# Pong_final.net
KiCad netlist of a schematic drawn in EAGLE
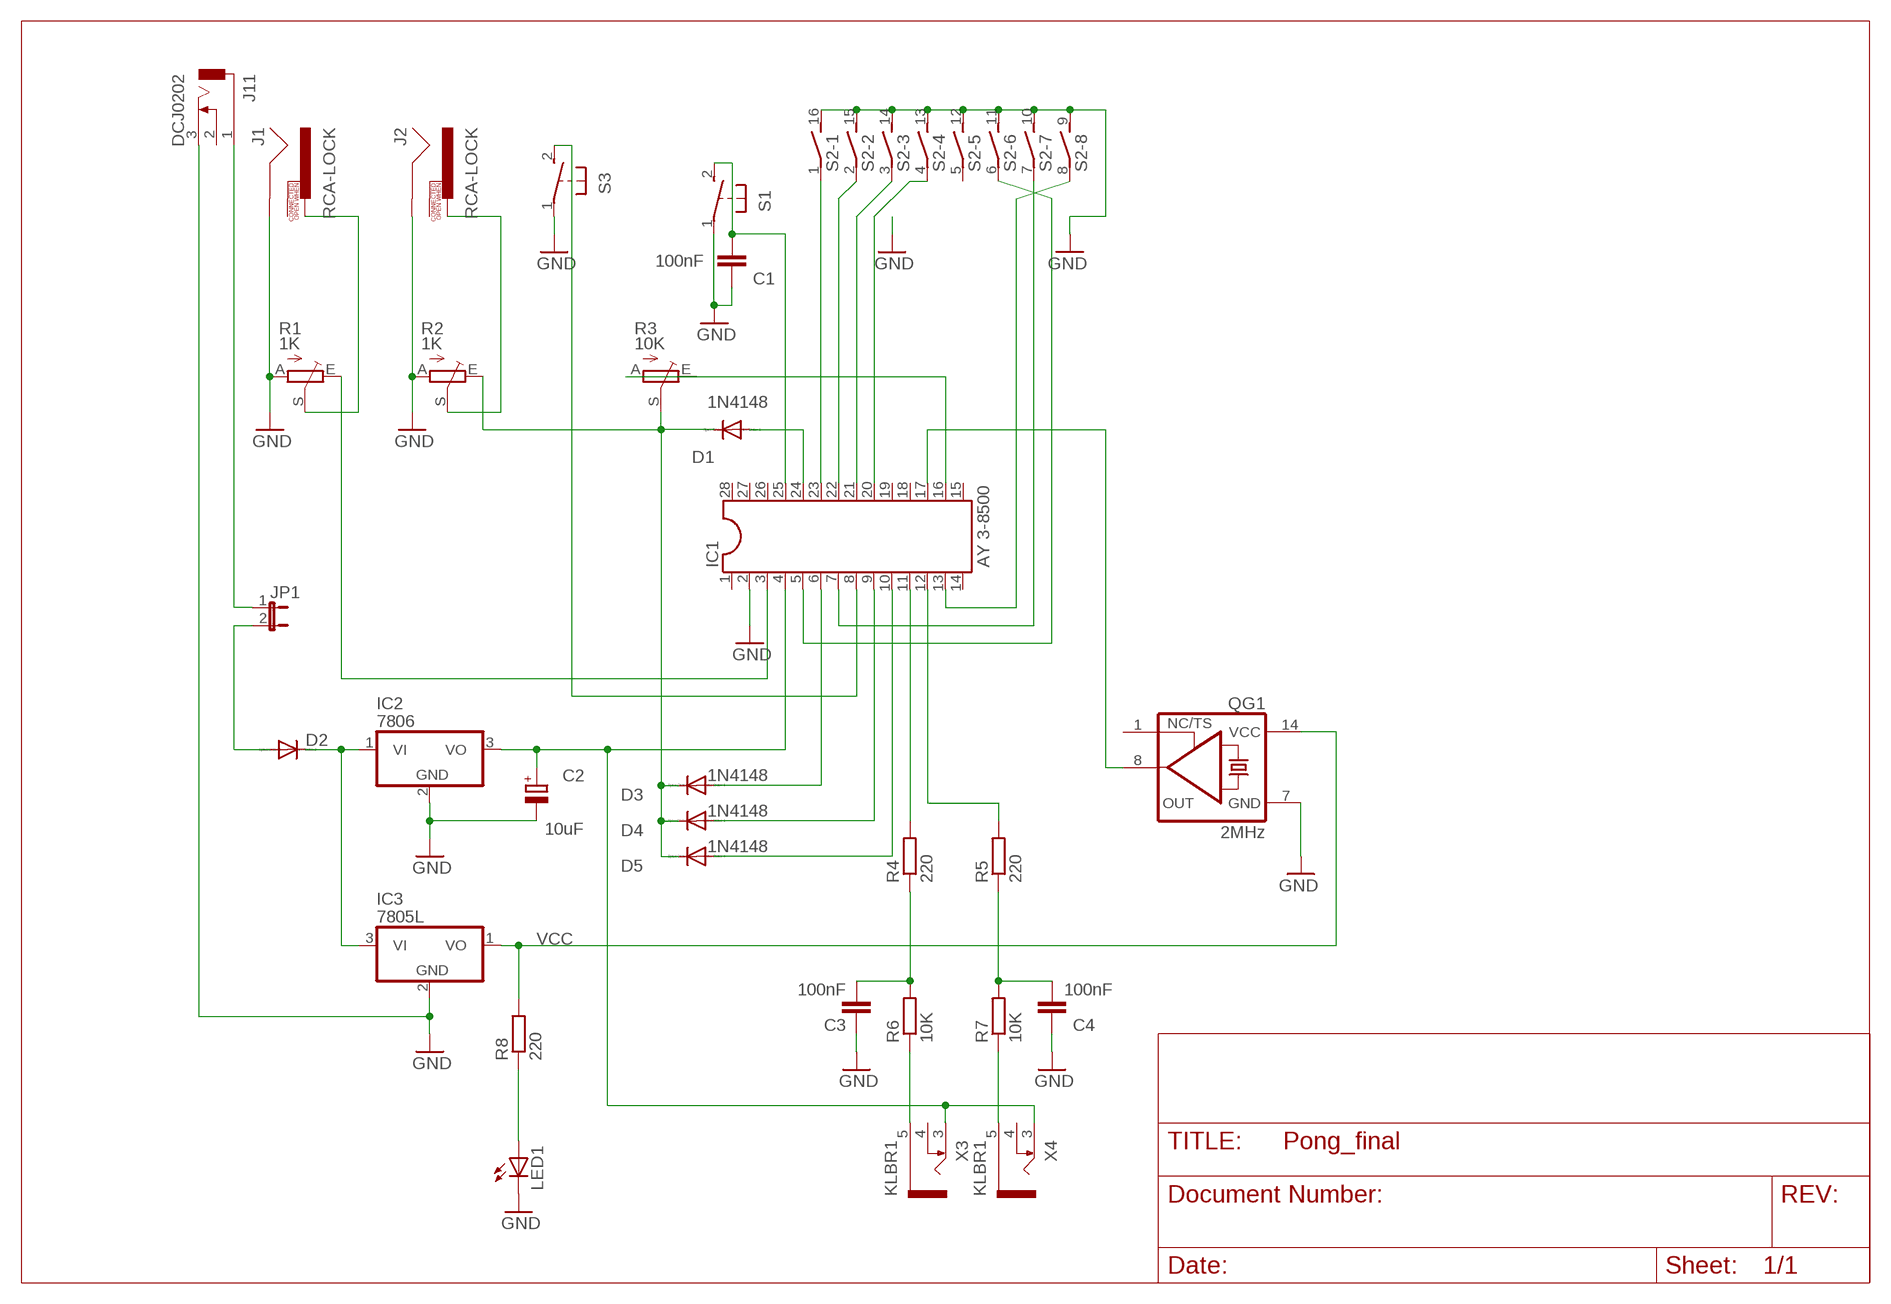
[diagram p0: schematic, sheet 1]

(export (version "E")
  (design (tool "Eeschema 10.0.6"))
  (components
    (comp (ref "C1")
      (value "100nF")
      (footprint "eagle-import:C0805")
      (libsource (lib "eagle-import") (part "C-EUC0805"))
    )
    (comp (ref "C2")
      (value "10uF")
      (footprint "eagle-import:E2,5-6")
      (libsource (lib "eagle-import") (part "CPOL-EUE2.5-6"))
    )
    (comp (ref "C3")
      (value "100nF")
      (footprint "eagle-import:C0805K")
      (libsource (lib "eagle-import") (part "C-EUC0805K"))
    )
    (comp (ref "C4")
      (value "100nF")
      (footprint "eagle-import:C0805K")
      (libsource (lib "eagle-import") (part "C-EUC0805K"))
    )
    (comp (ref "D1")
      (value "1N4148")
      (footprint "eagle-import:MINIMELF")
      (libsource (lib "eagle-import") (part "DIODE-MINIMELF"))
    )
    (comp (ref "D2")
      (value "DIODE-MELF-MLL41")
      (footprint "eagle-import:MELF-MLL41")
      (libsource (lib "eagle-import") (part "DIODE-MELF-MLL41"))
    )
    (comp (ref "D3")
      (value "1N4148")
      (footprint "eagle-import:MINIMELF")
      (libsource (lib "eagle-import") (part "DIODE-MINIMELF"))
    )
    (comp (ref "D4")
      (value "1N4148")
      (footprint "eagle-import:MINIMELF")
      (libsource (lib "eagle-import") (part "DIODE-MINIMELF"))
    )
    (comp (ref "D5")
      (value "1N4148")
      (footprint "eagle-import:MINIMELF")
      (libsource (lib "eagle-import") (part "DIODE-MINIMELF"))
    )
    (comp (ref "IC1")
      (value "AY 3-8500")
      (footprint "eagle-import:DIL28-6")
      (libsource (lib "eagle-import") (part "DIL28"))
    )
    (comp (ref "IC2")
      (value "7806")
      (footprint "eagle-import:TO220V")
      (libsource (lib "eagle-import") (part "78TV05"))
    )
    (comp (ref "IC3")
      (value "7805L")
      (footprint "eagle-import:TO92")
      (libsource (lib "eagle-import") (part "78L05"))
    )
    (comp (ref "J1")
      (value "RCA-LOCK")
      (footprint "eagle-import:RCA_LOCK")
      (libsource (lib "eagle-import") (part "RCA-LOCK"))
    )
    (comp (ref "J2")
      (value "RCA-LOCK")
      (footprint "eagle-import:RCA_LOCK")
      (libsource (lib "eagle-import") (part "RCA-LOCK"))
    )
    (comp (ref "J11")
      (value "DCJ0202")
      (footprint "eagle-import:DCJ0202")
      (libsource (lib "eagle-import") (part "DCJ0202"))
    )
    (comp (ref "JP1")
      (value "JP1E")
      (footprint "eagle-import:JP1")
      (libsource (lib "eagle-import") (part "JP1E"))
    )
    (comp (ref "LED1")
      (value "LEDB155")
      (footprint "eagle-import:Q62902-B155")
      (libsource (lib "eagle-import") (part "LEDB155"))
    )
    (comp (ref "QG1")
      (value "2MHz")
      (footprint "eagle-import:DIL14S")
      (libsource (lib "eagle-import") (part "XO-14"))
    )
    (comp (ref "R1")
      (value "1K")
      (footprint "eagle-import:CA6V")
      (libsource (lib "eagle-import") (part "TRIM_EU-CA6V"))
    )
    (comp (ref "R2")
      (value "1K")
      (footprint "eagle-import:CA6V")
      (libsource (lib "eagle-import") (part "TRIM_EU-CA6V"))
    )
    (comp (ref "R3")
      (value "10K")
      (footprint "eagle-import:CA6V")
      (libsource (lib "eagle-import") (part "TRIM_EU-CA6V"))
    )
    (comp (ref "R4")
      (value "220")
      (footprint "eagle-import:R0805")
      (libsource (lib "eagle-import") (part "R-EU_R0805"))
    )
    (comp (ref "R5")
      (value "220")
      (footprint "eagle-import:R0805")
      (libsource (lib "eagle-import") (part "R-EU_R0805"))
    )
    (comp (ref "R6")
      (value "10K")
      (footprint "eagle-import:R0805")
      (libsource (lib "eagle-import") (part "R-EU_R0805"))
    )
    (comp (ref "R7")
      (value "10K")
      (footprint "eagle-import:R0805")
      (libsource (lib "eagle-import") (part "R-EU_R0805"))
    )
    (comp (ref "R8")
      (value "220")
      (footprint "eagle-import:R0805")
      (libsource (lib "eagle-import") (part "R-EU_R0805"))
    )
    (comp (ref "S1")
      (value "31-XX")
      (footprint "eagle-import:B3F-31XX")
      (fields (field (name "MPN") "B3F-3100"))
      (libsource (lib "eagle-import") (part "31-XX"))
    )
    (comp (ref "S2")
      (value "DIP08S")
      (footprint "eagle-import:DIP08S")
      (libsource (lib "eagle-import") (part "DIP08S"))
    )
    (comp (ref "S3")
      (value "31-XX")
      (footprint "eagle-import:B3F-31XX")
      (fields (field (name "MPN") "B3F-3100"))
      (libsource (lib "eagle-import") (part "31-XX"))
    )
    (comp (ref "X3")
      (value "KLBR1")
      (footprint "eagle-import:KLBR1")
      (fields (field (name "MPN") "KLBR 1"))
      (libsource (lib "eagle-import") (part "KLBR?1"))
    )
    (comp (ref "X4")
      (value "KLBR1")
      (footprint "eagle-import:KLBR1")
      (fields (field (name "MPN") "KLBR 1"))
      (libsource (lib "eagle-import") (part "KLBR?1"))
    )
  )
  (nets
    (net (code "1") (name "/VCC") (class "Default")
      (node (ref "IC3") (pin "1") (pinfunction "VO_1") (pintype "passive"))
      (node (ref "QG1") (pin "14") (pinfunction "VCC_14") (pintype "power_in"))
      (node (ref "R8") (pin "2") (pinfunction "2_2") (pintype "passive"))
    )
    (net (code "2") (name "GND") (class "Default")
      (node (ref "C1") (pin "1") (pinfunction "1_1") (pintype "passive"))
      (node (ref "C2") (pin "-") (pinfunction "-_-") (pintype "passive"))
      (node (ref "C3") (pin "1") (pinfunction "1_1") (pintype "passive"))
      (node (ref "C4") (pin "1") (pinfunction "1_1") (pintype "passive"))
      (node (ref "IC1") (pin "2") (pinfunction "2_2") (pintype "passive"))
      (node (ref "IC2") (pin "2") (pinfunction "GND_2") (pintype "passive"))
      (node (ref "IC3") (pin "2") (pinfunction "GND_2") (pintype "passive"))
      (node (ref "J1") (pin "SHELL") (pinfunction "SHELL_SHELL") (pintype "bidirectional"))
      (node (ref "J11") (pin "3") (pinfunction "3_3") (pintype "passive"))
      (node (ref "J2") (pin "SHELL") (pinfunction "SHELL_SHELL") (pintype "bidirectional"))
      (node (ref "LED1") (pin "K") (pinfunction "C_K") (pintype "passive"))
      (node (ref "QG1") (pin "7") (pinfunction "GND_7") (pintype "power_in"))
      (node (ref "R1") (pin "A") (pinfunction "A_A") (pintype "passive"))
      (node (ref "R2") (pin "A") (pinfunction "A_A") (pintype "passive"))
      (node (ref "S1") (pin "1") (pinfunction "P_1") (pintype "passive"))
      (node (ref "S2") (pin "10") (pinfunction "2_10") (pintype "passive"))
      (node (ref "S2") (pin "11") (pinfunction "2_11") (pintype "passive"))
      (node (ref "S2") (pin "12") (pinfunction "2_12") (pintype "passive"))
      (node (ref "S2") (pin "13") (pinfunction "2_13") (pintype "passive"))
      (node (ref "S2") (pin "14") (pinfunction "2_14") (pintype "passive"))
      (node (ref "S2") (pin "15") (pinfunction "2_15") (pintype "passive"))
      (node (ref "S2") (pin "16") (pinfunction "2_16") (pintype "passive"))
      (node (ref "S2") (pin "9") (pinfunction "2_9") (pintype "passive"))
      (node (ref "S3") (pin "1") (pinfunction "P_1") (pintype "passive"))
    )
    (net (code "3") (name "Net-(C3-Pad2)") (class "Default")
      (node (ref "C3") (pin "2") (pinfunction "2_2") (pintype "passive"))
      (node (ref "R4") (pin "1") (pinfunction "1_1") (pintype "passive"))
      (node (ref "R6") (pin "2") (pinfunction "2_2") (pintype "passive"))
    )
    (net (code "4") (name "Net-(C4-Pad2)") (class "Default")
      (node (ref "C4") (pin "2") (pinfunction "2_2") (pintype "passive"))
      (node (ref "R5") (pin "1") (pinfunction "1_1") (pintype "passive"))
      (node (ref "R7") (pin "2") (pinfunction "2_2") (pintype "passive"))
    )
    (net (code "5") (name "Net-(D1-PadA)") (class "Default")
      (node (ref "D1") (pin "A") (pinfunction "A_A") (pintype "passive"))
      (node (ref "IC1") (pin "24") (pinfunction "24_24") (pintype "passive"))
    )
    (net (code "6") (name "Net-(D1-PadC)") (class "Default")
      (node (ref "D1") (pin "C") (pinfunction "C_C") (pintype "passive"))
      (node (ref "D3") (pin "C") (pinfunction "C_C") (pintype "passive"))
      (node (ref "D4") (pin "C") (pinfunction "C_C") (pintype "passive"))
      (node (ref "D5") (pin "C") (pinfunction "C_C") (pintype "passive"))
      (node (ref "R2") (pin "E") (pinfunction "E_E") (pintype "passive"))
      (node (ref "R3") (pin "S") (pinfunction "S_S") (pintype "passive"))
    )
    (net (code "7") (name "Net-(D2-PadA)") (class "Default")
      (node (ref "D2") (pin "A") (pinfunction "A_A") (pintype "passive"))
      (node (ref "JP1") (pin "2") (pinfunction "2_2") (pintype "passive"))
    )
    (net (code "8") (name "Net-(D3-PadA)") (class "Default")
      (node (ref "D3") (pin "A") (pinfunction "A_A") (pintype "passive"))
      (node (ref "IC1") (pin "6") (pinfunction "6_6") (pintype "passive"))
    )
    (net (code "9") (name "Net-(D4-PadA)") (class "Default")
      (node (ref "D4") (pin "A") (pinfunction "A_A") (pintype "passive"))
      (node (ref "IC1") (pin "9") (pinfunction "9_9") (pintype "passive"))
    )
    (net (code "10") (name "Net-(D5-PadA)") (class "Default")
      (node (ref "D5") (pin "A") (pinfunction "A_A") (pintype "passive"))
      (node (ref "IC1") (pin "10") (pinfunction "10_10") (pintype "passive"))
    )
    (net (code "11") (name "Net-(IC1-Pad3)") (class "Default")
      (node (ref "IC1") (pin "3") (pinfunction "3_3") (pintype "passive"))
      (node (ref "R1") (pin "E") (pinfunction "E_E") (pintype "passive"))
    )
    (net (code "12") (name "Net-(IC1-Pad11)") (class "Default")
      (node (ref "IC1") (pin "11") (pinfunction "11_11") (pintype "passive"))
      (node (ref "R4") (pin "2") (pinfunction "2_2") (pintype "passive"))
    )
    (net (code "13") (name "Net-(IC1-Pad12)") (class "Default")
      (node (ref "IC1") (pin "12") (pinfunction "12_12") (pintype "passive"))
      (node (ref "R5") (pin "2") (pinfunction "2_2") (pintype "passive"))
    )
    (net (code "14") (name "Net-(IC1-Pad16)") (class "Default")
      (node (ref "IC1") (pin "16") (pinfunction "16_16") (pintype "passive"))
      (node (ref "R3") (pin "A") (pinfunction "A_A") (pintype "passive"))
    )
    (net (code "15") (name "Net-(IC1-Pad23)") (class "Default")
      (node (ref "IC1") (pin "23") (pinfunction "23_23") (pintype "passive"))
      (node (ref "S2") (pin "1") (pinfunction "1_1") (pintype "passive"))
    )
    (net (code "16") (name "Net-(IC2-VI)") (class "Default")
      (node (ref "D2") (pin "C") (pinfunction "C_C") (pintype "passive"))
      (node (ref "IC2") (pin "1") (pinfunction "VI_1") (pintype "input"))
      (node (ref "IC3") (pin "3") (pinfunction "VI_3") (pintype "input"))
    )
    (net (code "17") (name "Net-(IC2-VO)") (class "Default")
      (node (ref "C2") (pin "+") (pinfunction "+_+") (pintype "passive"))
      (node (ref "IC1") (pin "4") (pinfunction "4_4") (pintype "passive"))
      (node (ref "IC2") (pin "3") (pinfunction "VO_3") (pintype "passive"))
      (node (ref "X3") (pin "3") (pinfunction "3_3") (pintype "passive"))
      (node (ref "X4") (pin "3") (pinfunction "3_3") (pintype "passive"))
    )
    (net (code "18") (name "Net-(J1-PadPIN)") (class "Default")
      (node (ref "J1") (pin "PIN") (pinfunction "PIN_PIN") (pintype "bidirectional"))
      (node (ref "R1") (pin "S") (pinfunction "S_S") (pintype "passive"))
    )
    (net (code "19") (name "Net-(J2-PadPIN)") (class "Default")
      (node (ref "J2") (pin "PIN") (pinfunction "PIN_PIN") (pintype "bidirectional"))
      (node (ref "R2") (pin "S") (pinfunction "S_S") (pintype "passive"))
    )
    (net (code "20") (name "Net-(J11-Pad1)") (class "Default")
      (node (ref "J11") (pin "1") (pinfunction "1_1") (pintype "passive"))
      (node (ref "JP1") (pin "1") (pinfunction "1_1") (pintype "passive"))
    )
    (net (code "21") (name "Net-(LED1-PadA)") (class "Default")
      (node (ref "LED1") (pin "A") (pinfunction "A_A") (pintype "passive"))
      (node (ref "R8") (pin "1") (pinfunction "1_1") (pintype "passive"))
    )
    (net (code "22") (name "Net-(QG1-OUT)") (class "Default")
      (node (ref "IC1") (pin "17") (pinfunction "17_17") (pintype "passive"))
      (node (ref "QG1") (pin "8") (pinfunction "OUT_8") (pintype "output"))
    )
    (net (code "23") (name "Net-(R6-Pad1)") (class "Default")
      (node (ref "R6") (pin "1") (pinfunction "1_1") (pintype "passive"))
      (node (ref "X3") (pin "5") (pinfunction "5_5") (pintype "passive"))
    )
    (net (code "24") (name "Net-(R7-Pad1)") (class "Default")
      (node (ref "R7") (pin "1") (pinfunction "1_1") (pintype "passive"))
      (node (ref "X4") (pin "5") (pinfunction "5_5") (pintype "passive"))
    )
    (net (code "25") (name "Net-(S1-S)") (class "Default")
      (node (ref "C1") (pin "2") (pinfunction "2_2") (pintype "passive"))
      (node (ref "IC1") (pin "25") (pinfunction "25_25") (pintype "passive"))
      (node (ref "S1") (pin "2") (pinfunction "S_2") (pintype "passive"))
    )
    (net (code "26") (name "Net-(S2B-1)") (class "Default")
      (node (ref "IC1") (pin "22") (pinfunction "22_22") (pintype "passive"))
      (node (ref "S2") (pin "2") (pinfunction "1_2") (pintype "passive"))
    )
    (net (code "27") (name "Net-(S2C-1)") (class "Default")
      (node (ref "IC1") (pin "21") (pinfunction "21_21") (pintype "passive"))
      (node (ref "S2") (pin "3") (pinfunction "1_3") (pintype "passive"))
    )
    (net (code "28") (name "Net-(S2D-1)") (class "Default")
      (node (ref "IC1") (pin "20") (pinfunction "20_20") (pintype "passive"))
      (node (ref "S2") (pin "4") (pinfunction "1_4") (pintype "passive"))
    )
    (net (code "29") (name "Net-(S2F-1)") (class "Default")
      (node (ref "IC1") (pin "5") (pinfunction "5_5") (pintype "passive"))
      (node (ref "S2") (pin "6") (pinfunction "1_6") (pintype "passive"))
    )
    (net (code "30") (name "Net-(S2G-1)") (class "Default")
      (node (ref "IC1") (pin "7") (pinfunction "7_7") (pintype "passive"))
      (node (ref "S2") (pin "7") (pinfunction "1_7") (pintype "passive"))
    )
    (net (code "31") (name "Net-(S2H-1)") (class "Default")
      (node (ref "IC1") (pin "13") (pinfunction "13_13") (pintype "passive"))
      (node (ref "S2") (pin "8") (pinfunction "1_8") (pintype "passive"))
    )
    (net (code "32") (name "Net-(S3-S)") (class "Default")
      (node (ref "IC1") (pin "8") (pinfunction "8_8") (pintype "passive"))
      (node (ref "S3") (pin "2") (pinfunction "S_2") (pintype "passive"))
    )
    (net (code "33") (name "unconnected-(IC1-Pad1)") (class "Default")
      (node (ref "IC1") (pin "1") (pinfunction "1_1") (pintype "passive"))
    )
    (net (code "34") (name "unconnected-(IC1-Pad14)") (class "Default")
      (node (ref "IC1") (pin "14") (pinfunction "14_14") (pintype "passive"))
    )
    (net (code "35") (name "unconnected-(IC1-Pad15)") (class "Default")
      (node (ref "IC1") (pin "15") (pinfunction "15_15") (pintype "passive"))
    )
    (net (code "36") (name "unconnected-(IC1-Pad18)") (class "Default")
      (node (ref "IC1") (pin "18") (pinfunction "18_18") (pintype "passive"))
    )
    (net (code "37") (name "unconnected-(IC1-Pad19)") (class "Default")
      (node (ref "IC1") (pin "19") (pinfunction "19_19") (pintype "passive"))
    )
    (net (code "38") (name "unconnected-(IC1-Pad26)") (class "Default")
      (node (ref "IC1") (pin "26") (pinfunction "26_26") (pintype "passive"))
    )
    (net (code "39") (name "unconnected-(IC1-Pad27)") (class "Default")
      (node (ref "IC1") (pin "27") (pinfunction "27_27") (pintype "passive"))
    )
    (net (code "40") (name "unconnected-(IC1-Pad28)") (class "Default")
      (node (ref "IC1") (pin "28") (pinfunction "28_28") (pintype "passive"))
    )
    (net (code "41") (name "unconnected-(J1-PadSWITCH)") (class "Default")
      (node (ref "J1") (pin "SWITCH") (pinfunction "SWITCH_SWITCH") (pintype "bidirectional"))
    )
    (net (code "42") (name "unconnected-(J2-PadSWITCH)") (class "Default")
      (node (ref "J2") (pin "SWITCH") (pinfunction "SWITCH_SWITCH") (pintype "bidirectional"))
    )
    (net (code "43") (name "unconnected-(J11-Pad2)") (class "Default")
      (node (ref "J11") (pin "2") (pinfunction "2_2") (pintype "passive"))
    )
    (net (code "44") (name "unconnected-(QG1-TS-Pad1)") (class "Default")
      (node (ref "QG1") (pin "1") (pinfunction "TS_1") (pintype "passive"))
    )
    (net (code "45") (name "unconnected-(R3-PadE)") (class "Default")
      (node (ref "R3") (pin "E") (pinfunction "E_E") (pintype "passive"))
    )
    (net (code "46") (name "unconnected-(S2E-1-Pad5)") (class "Default")
      (node (ref "S2") (pin "5") (pinfunction "1_5") (pintype "passive"))
    )
    (net (code "47") (name "unconnected-(X3-Pad4)") (class "Default")
      (node (ref "X3") (pin "4") (pinfunction "4_4") (pintype "passive"))
    )
    (net (code "48") (name "unconnected-(X4-Pad4)") (class "Default")
      (node (ref "X4") (pin "4") (pinfunction "4_4") (pintype "passive"))
    )
  )
)
